# SimpleCharger-LiIon-OpampBased-LM324.net
KiCad netlist of a schematic drawn in EAGLE
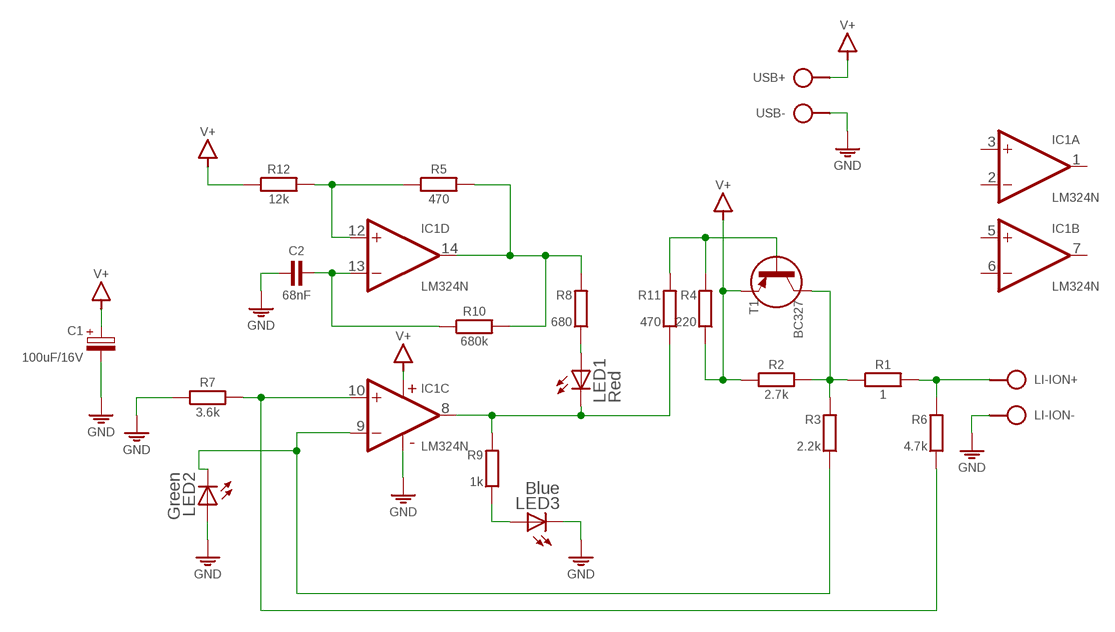
[diagram p0: schematic, sheet 1]

(export (version "E")
  (design (tool "Eeschema 10.0.6"))
  (components
    (comp (ref "C1")
      (value "100uF/16V")
      (footprint "eagle-import:E2,5-5")
      (libsource (lib "eagle-import") (part "CPOLE2.5-5"))
    )
    (comp (ref "C2")
      (value "68nF")
      (footprint "eagle-import:C050-020X044")
      (libsource (lib "eagle-import") (part "C-H050-020X044"))
    )
    (comp (ref "IC1")
      (value "LM324N")
      (footprint "eagle-import:DIL14")
      (libsource (lib "eagle-import") (part "LM324N"))
    )
    (comp (ref "LED1")
      (value "Red")
      (footprint "eagle-import:LED3MM")
      (libsource (lib "eagle-import") (part "LED3MM"))
    )
    (comp (ref "LED2")
      (value "Green")
      (footprint "eagle-import:LED3MM")
      (libsource (lib "eagle-import") (part "LED3MM"))
    )
    (comp (ref "LED3")
      (value "Blue")
      (footprint "eagle-import:LED3MM")
      (libsource (lib "eagle-import") (part "LED3MM"))
    )
    (comp (ref "LI-ION")
      (value "SPAD+-+-")
      (footprint "eagle-import:SPAD+-")
      (libsource (lib "eagle-import") (part "SPAD+-+-"))
    )
    (comp (ref "R1")
      (value "1")
      (footprint "eagle-import:0204_10")
      (libsource (lib "eagle-import") (part "R-H0204/10"))
    )
    (comp (ref "R2")
      (value "2.7k")
      (footprint "eagle-import:0204_10-V")
      (libsource (lib "eagle-import") (part "R-H0204/10-V"))
    )
    (comp (ref "R3")
      (value "2.2k")
      (footprint "eagle-import:0204_10-V")
      (libsource (lib "eagle-import") (part "R0204/10-V"))
    )
    (comp (ref "R4")
      (value "220")
      (footprint "eagle-import:0204_10-V")
      (libsource (lib "eagle-import") (part "R0204/10-V"))
    )
    (comp (ref "R5")
      (value "470")
      (footprint "eagle-import:0204_10")
      (libsource (lib "eagle-import") (part "R-H0204/10"))
    )
    (comp (ref "R6")
      (value "4.7k")
      (footprint "eagle-import:0204_10-V")
      (libsource (lib "eagle-import") (part "R0204/10-V"))
    )
    (comp (ref "R7")
      (value "3.6k")
      (footprint "eagle-import:0204_10")
      (libsource (lib "eagle-import") (part "R-H0204/10"))
    )
    (comp (ref "R8")
      (value "680")
      (footprint "eagle-import:0204_10-V")
      (libsource (lib "eagle-import") (part "R0204/10-V"))
    )
    (comp (ref "R9")
      (value "1k")
      (footprint "eagle-import:0204_7-V")
      (libsource (lib "eagle-import") (part "R0204/7-V"))
    )
    (comp (ref "R10")
      (value "680k")
      (footprint "eagle-import:0204_10")
      (libsource (lib "eagle-import") (part "R-H0204/10"))
    )
    (comp (ref "R11")
      (value "470")
      (footprint "eagle-import:0204_10-V")
      (libsource (lib "eagle-import") (part "R0204/10-V"))
    )
    (comp (ref "R12")
      (value "12k")
      (footprint "eagle-import:0204_10-V")
      (libsource (lib "eagle-import") (part "R-H0204/10-V"))
    )
    (comp (ref "T1")
      (value "BC327")
      (footprint "eagle-import:TO92")
      (libsource (lib "eagle-import") (part "BC327"))
    )
    (comp (ref "USB")
      (value "SPAD+--+")
      (footprint "eagle-import:SPAD-+")
      (libsource (lib "eagle-import") (part "SPAD+--+"))
    )
  )
  (nets
    (net (code "1") (name "GND") (class "Default")
      (node (ref "C1") (pin "-") (pinfunction "-_-") (pintype "passive"))
      (node (ref "C2") (pin "1") (pinfunction "1_1") (pintype "passive"))
      (node (ref "IC1") (pin "11") (pinfunction "V-_11") (pintype "power_in"))
      (node (ref "LED2") (pin "A") (pinfunction "A_A") (pintype "passive"))
      (node (ref "LED3") (pin "K") (pinfunction "C_K") (pintype "passive"))
      (node (ref "LI-ION") (pin "1") (pinfunction "P$1_1") (pintype "passive"))
      (node (ref "R7") (pin "1") (pinfunction "1_1") (pintype "passive"))
      (node (ref "USB") (pin "1") (pinfunction "P$1_1") (pintype "passive"))
    )
    (net (code "2") (name "Net-(IC1C-+IN)") (class "Default")
      (node (ref "IC1") (pin "10") (pinfunction "+IN_10") (pintype "input"))
      (node (ref "R6") (pin "2") (pinfunction "2_2") (pintype "passive"))
      (node (ref "R7") (pin "2") (pinfunction "2_2") (pintype "passive"))
    )
    (net (code "3") (name "Net-(IC1C--IN)") (class "Default")
      (node (ref "IC1") (pin "9") (pinfunction "-IN_9") (pintype "input"))
      (node (ref "LED2") (pin "K") (pinfunction "C_K") (pintype "passive"))
      (node (ref "R3") (pin "2") (pinfunction "2_2") (pintype "passive"))
    )
    (net (code "4") (name "Net-(IC1C-OUT)") (class "Default")
      (node (ref "IC1") (pin "8") (pinfunction "OUT_8") (pintype "output"))
      (node (ref "LED1") (pin "K") (pinfunction "C_K") (pintype "passive"))
      (node (ref "R11") (pin "2") (pinfunction "2_2") (pintype "passive"))
      (node (ref "R9") (pin "2") (pinfunction "1_2") (pintype "passive"))
    )
    (net (code "5") (name "Net-(IC1D-+IN)") (class "Default")
      (node (ref "IC1") (pin "12") (pinfunction "+IN_12") (pintype "input"))
      (node (ref "R12") (pin "2") (pinfunction "2_2") (pintype "passive"))
      (node (ref "R5") (pin "1") (pinfunction "1_1") (pintype "passive"))
    )
    (net (code "6") (name "Net-(IC1D--IN)") (class "Default")
      (node (ref "C2") (pin "2") (pinfunction "2_2") (pintype "passive"))
      (node (ref "IC1") (pin "13") (pinfunction "-IN_13") (pintype "input"))
      (node (ref "R10") (pin "1") (pinfunction "1_1") (pintype "passive"))
    )
    (net (code "7") (name "Net-(IC1D-OUT)") (class "Default")
      (node (ref "IC1") (pin "14") (pinfunction "OUT_14") (pintype "output"))
      (node (ref "R10") (pin "2") (pinfunction "2_2") (pintype "passive"))
      (node (ref "R5") (pin "2") (pinfunction "2_2") (pintype "passive"))
      (node (ref "R8") (pin "1") (pinfunction "1_1") (pintype "passive"))
    )
    (net (code "8") (name "Net-(LED1-PadA)") (class "Default")
      (node (ref "LED1") (pin "A") (pinfunction "A_A") (pintype "passive"))
      (node (ref "R8") (pin "2") (pinfunction "2_2") (pintype "passive"))
    )
    (net (code "9") (name "Net-(LI-IONA-P$1)") (class "Default")
      (node (ref "LI-ION") (pin "2") (pinfunction "P$1_2") (pintype "passive"))
      (node (ref "R1") (pin "2") (pinfunction "2_2") (pintype "passive"))
      (node (ref "R6") (pin "1") (pinfunction "1_1") (pintype "passive"))
    )
    (net (code "10") (name "Net-(R9-2)") (class "Default")
      (node (ref "LED3") (pin "A") (pinfunction "A_A") (pintype "passive"))
      (node (ref "R9") (pin "1") (pinfunction "2_1") (pintype "passive"))
    )
    (net (code "11") (name "Net-(T1-B)") (class "Default")
      (node (ref "R11") (pin "1") (pinfunction "1_1") (pintype "passive"))
      (node (ref "R4") (pin "1") (pinfunction "1_1") (pintype "passive"))
      (node (ref "T1") (pin "2") (pinfunction "B_2") (pintype "passive"))
    )
    (net (code "12") (name "Net-(T1-C)") (class "Default")
      (node (ref "R1") (pin "1") (pinfunction "1_1") (pintype "passive"))
      (node (ref "R2") (pin "2") (pinfunction "2_2") (pintype "passive"))
      (node (ref "R3") (pin "1") (pinfunction "1_1") (pintype "passive"))
      (node (ref "T1") (pin "1") (pinfunction "C_1") (pintype "passive"))
    )
    (net (code "13") (name "V+") (class "Default")
      (node (ref "C1") (pin "+") (pinfunction "+_+") (pintype "passive"))
      (node (ref "IC1") (pin "4") (pinfunction "V+_4") (pintype "power_in"))
      (node (ref "R12") (pin "1") (pinfunction "1_1") (pintype "passive"))
      (node (ref "R2") (pin "1") (pinfunction "1_1") (pintype "passive"))
      (node (ref "R4") (pin "2") (pinfunction "2_2") (pintype "passive"))
      (node (ref "T1") (pin "3") (pinfunction "E_3") (pintype "passive"))
      (node (ref "USB") (pin "2") (pinfunction "P$1_2") (pintype "passive"))
    )
    (net (code "14") (name "unconnected-(IC1A-+IN-Pad3)") (class "Default")
      (node (ref "IC1") (pin "3") (pinfunction "+IN_3") (pintype "input"))
    )
    (net (code "15") (name "unconnected-(IC1A--IN-Pad2)") (class "Default")
      (node (ref "IC1") (pin "2") (pinfunction "-IN_2") (pintype "input"))
    )
    (net (code "16") (name "unconnected-(IC1A-OUT-Pad1)") (class "Default")
      (node (ref "IC1") (pin "1") (pinfunction "OUT_1") (pintype "output"))
    )
    (net (code "17") (name "unconnected-(IC1B-+IN-Pad5)") (class "Default")
      (node (ref "IC1") (pin "5") (pinfunction "+IN_5") (pintype "input"))
    )
    (net (code "18") (name "unconnected-(IC1B--IN-Pad6)") (class "Default")
      (node (ref "IC1") (pin "6") (pinfunction "-IN_6") (pintype "input"))
    )
    (net (code "19") (name "unconnected-(IC1B-OUT-Pad7)") (class "Default")
      (node (ref "IC1") (pin "7") (pinfunction "OUT_7") (pintype "output"))
    )
  )
)
